# ProProject_ExtBoard-003_2024-07-01.net
KiCad netlist of a schematic drawn in EasyEDA Pro
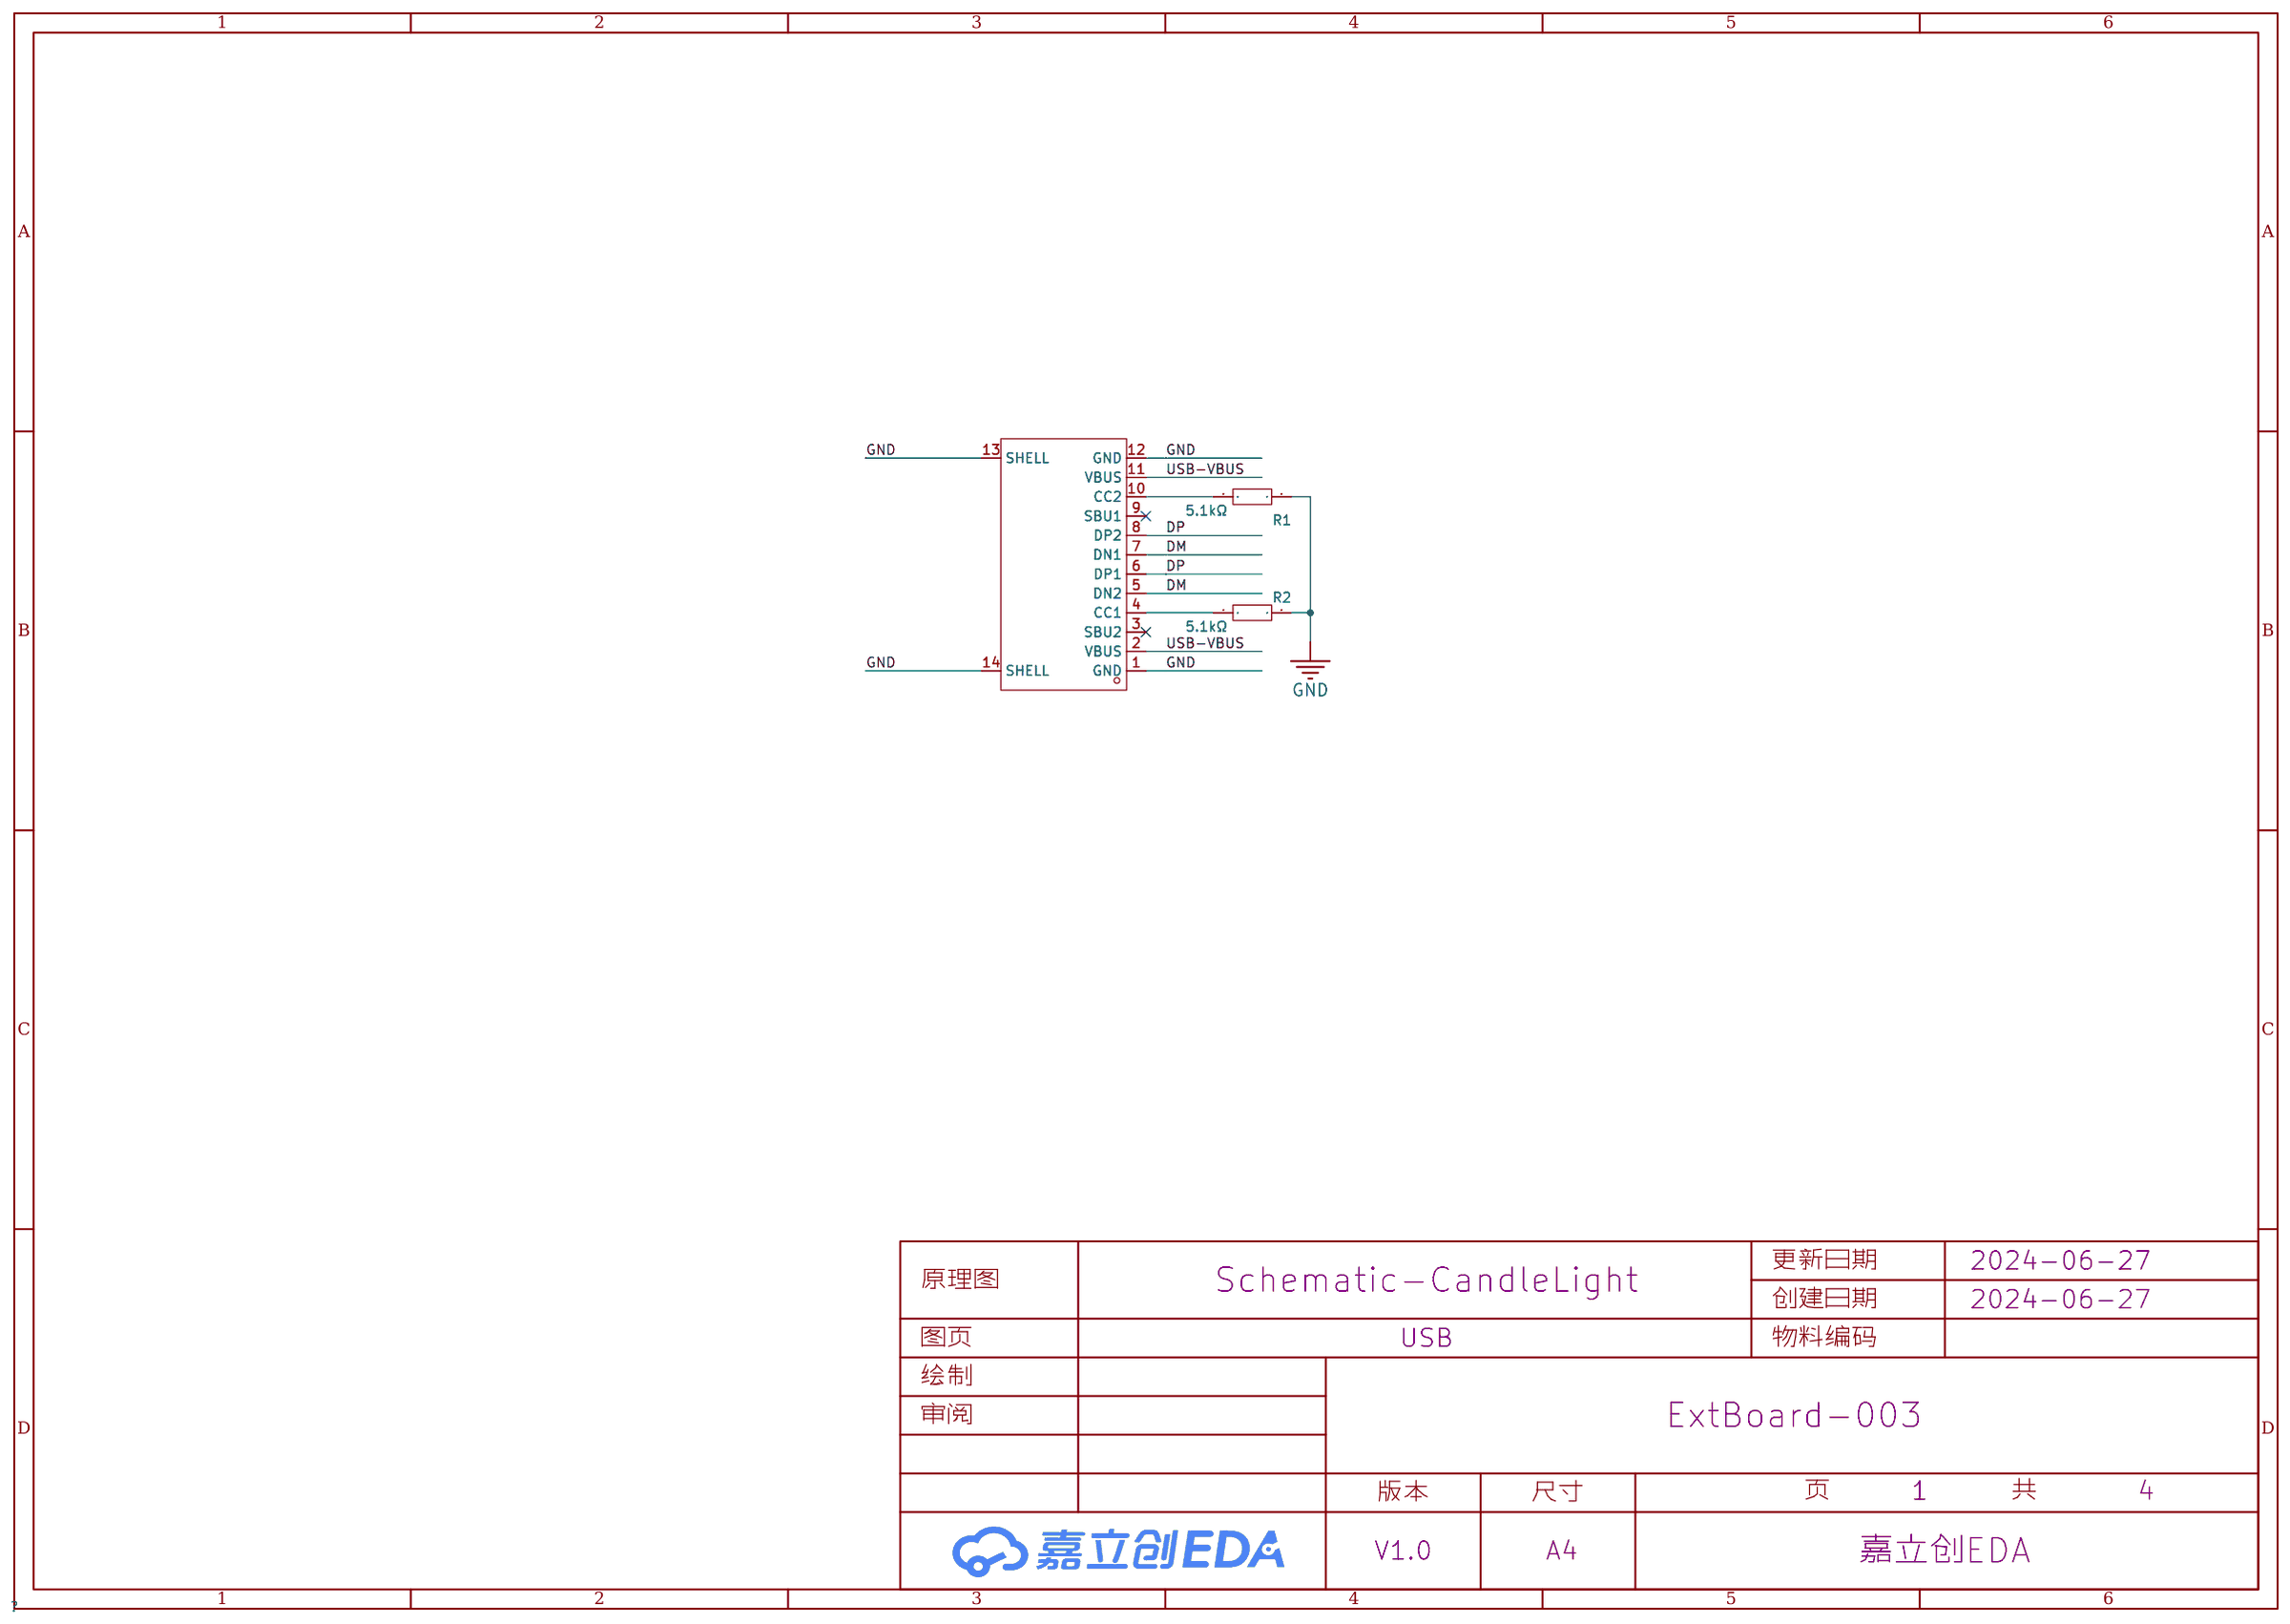
[diagram p0: USB]
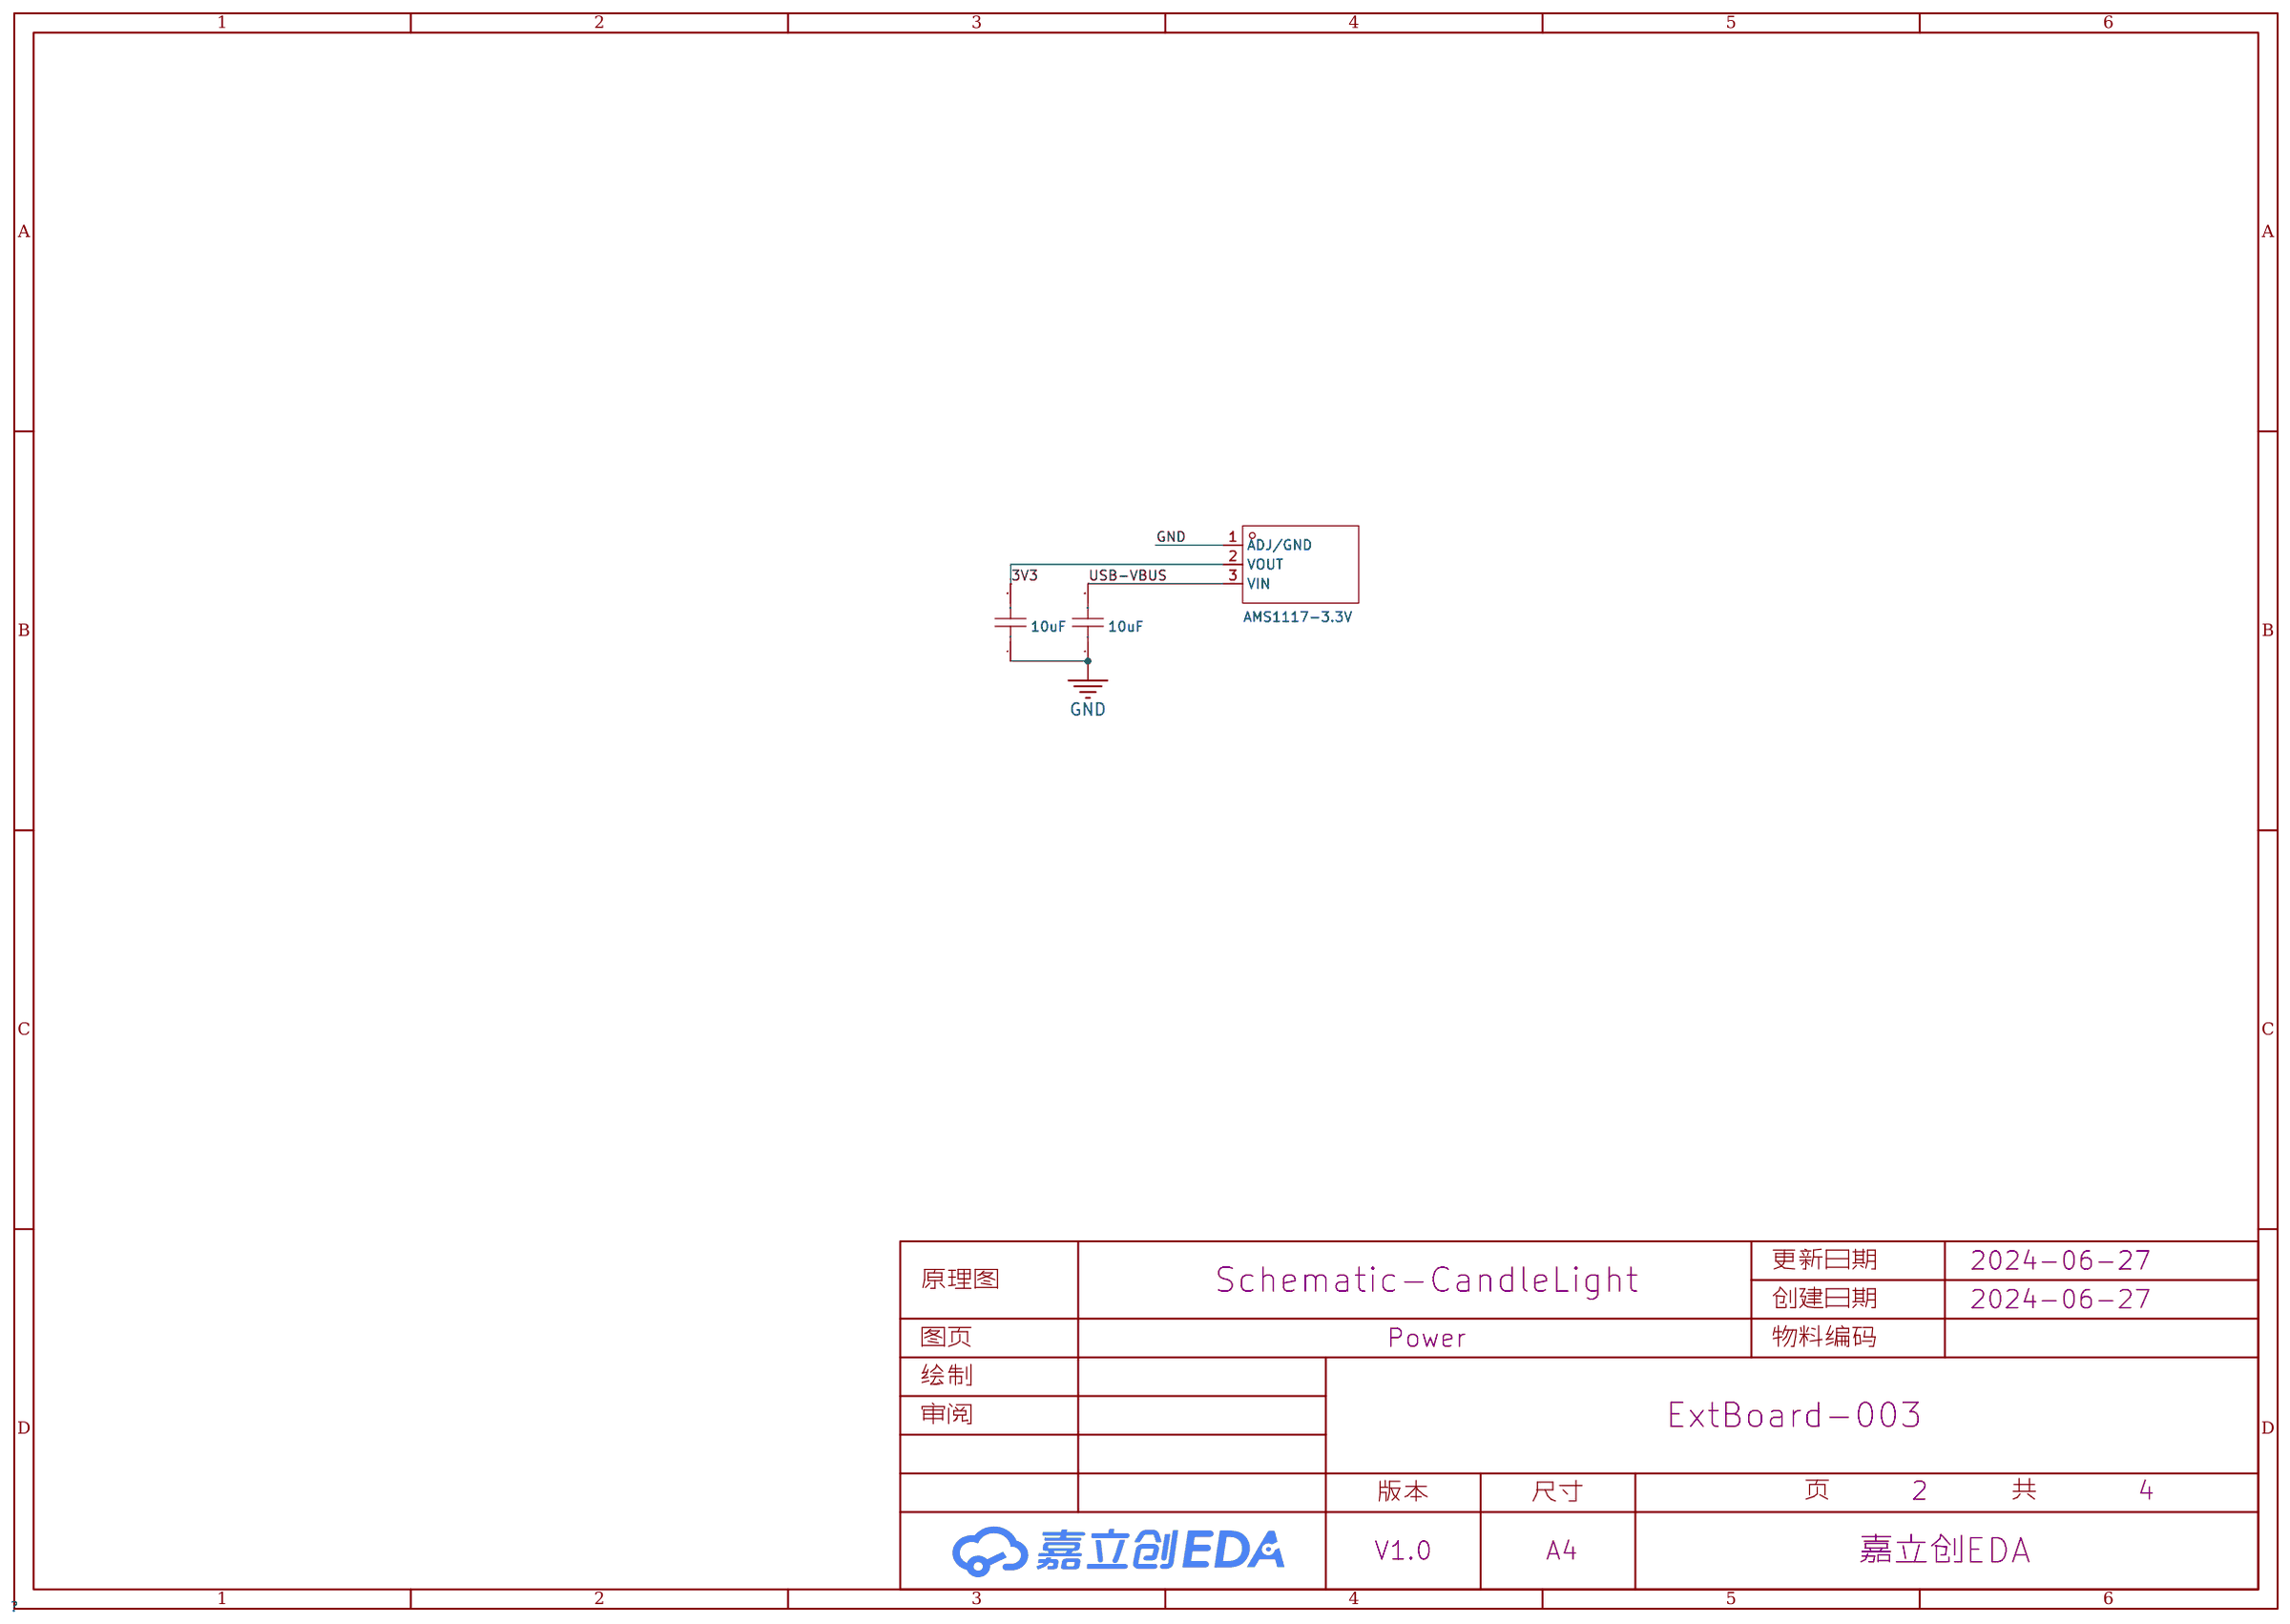
[diagram p1: Power]
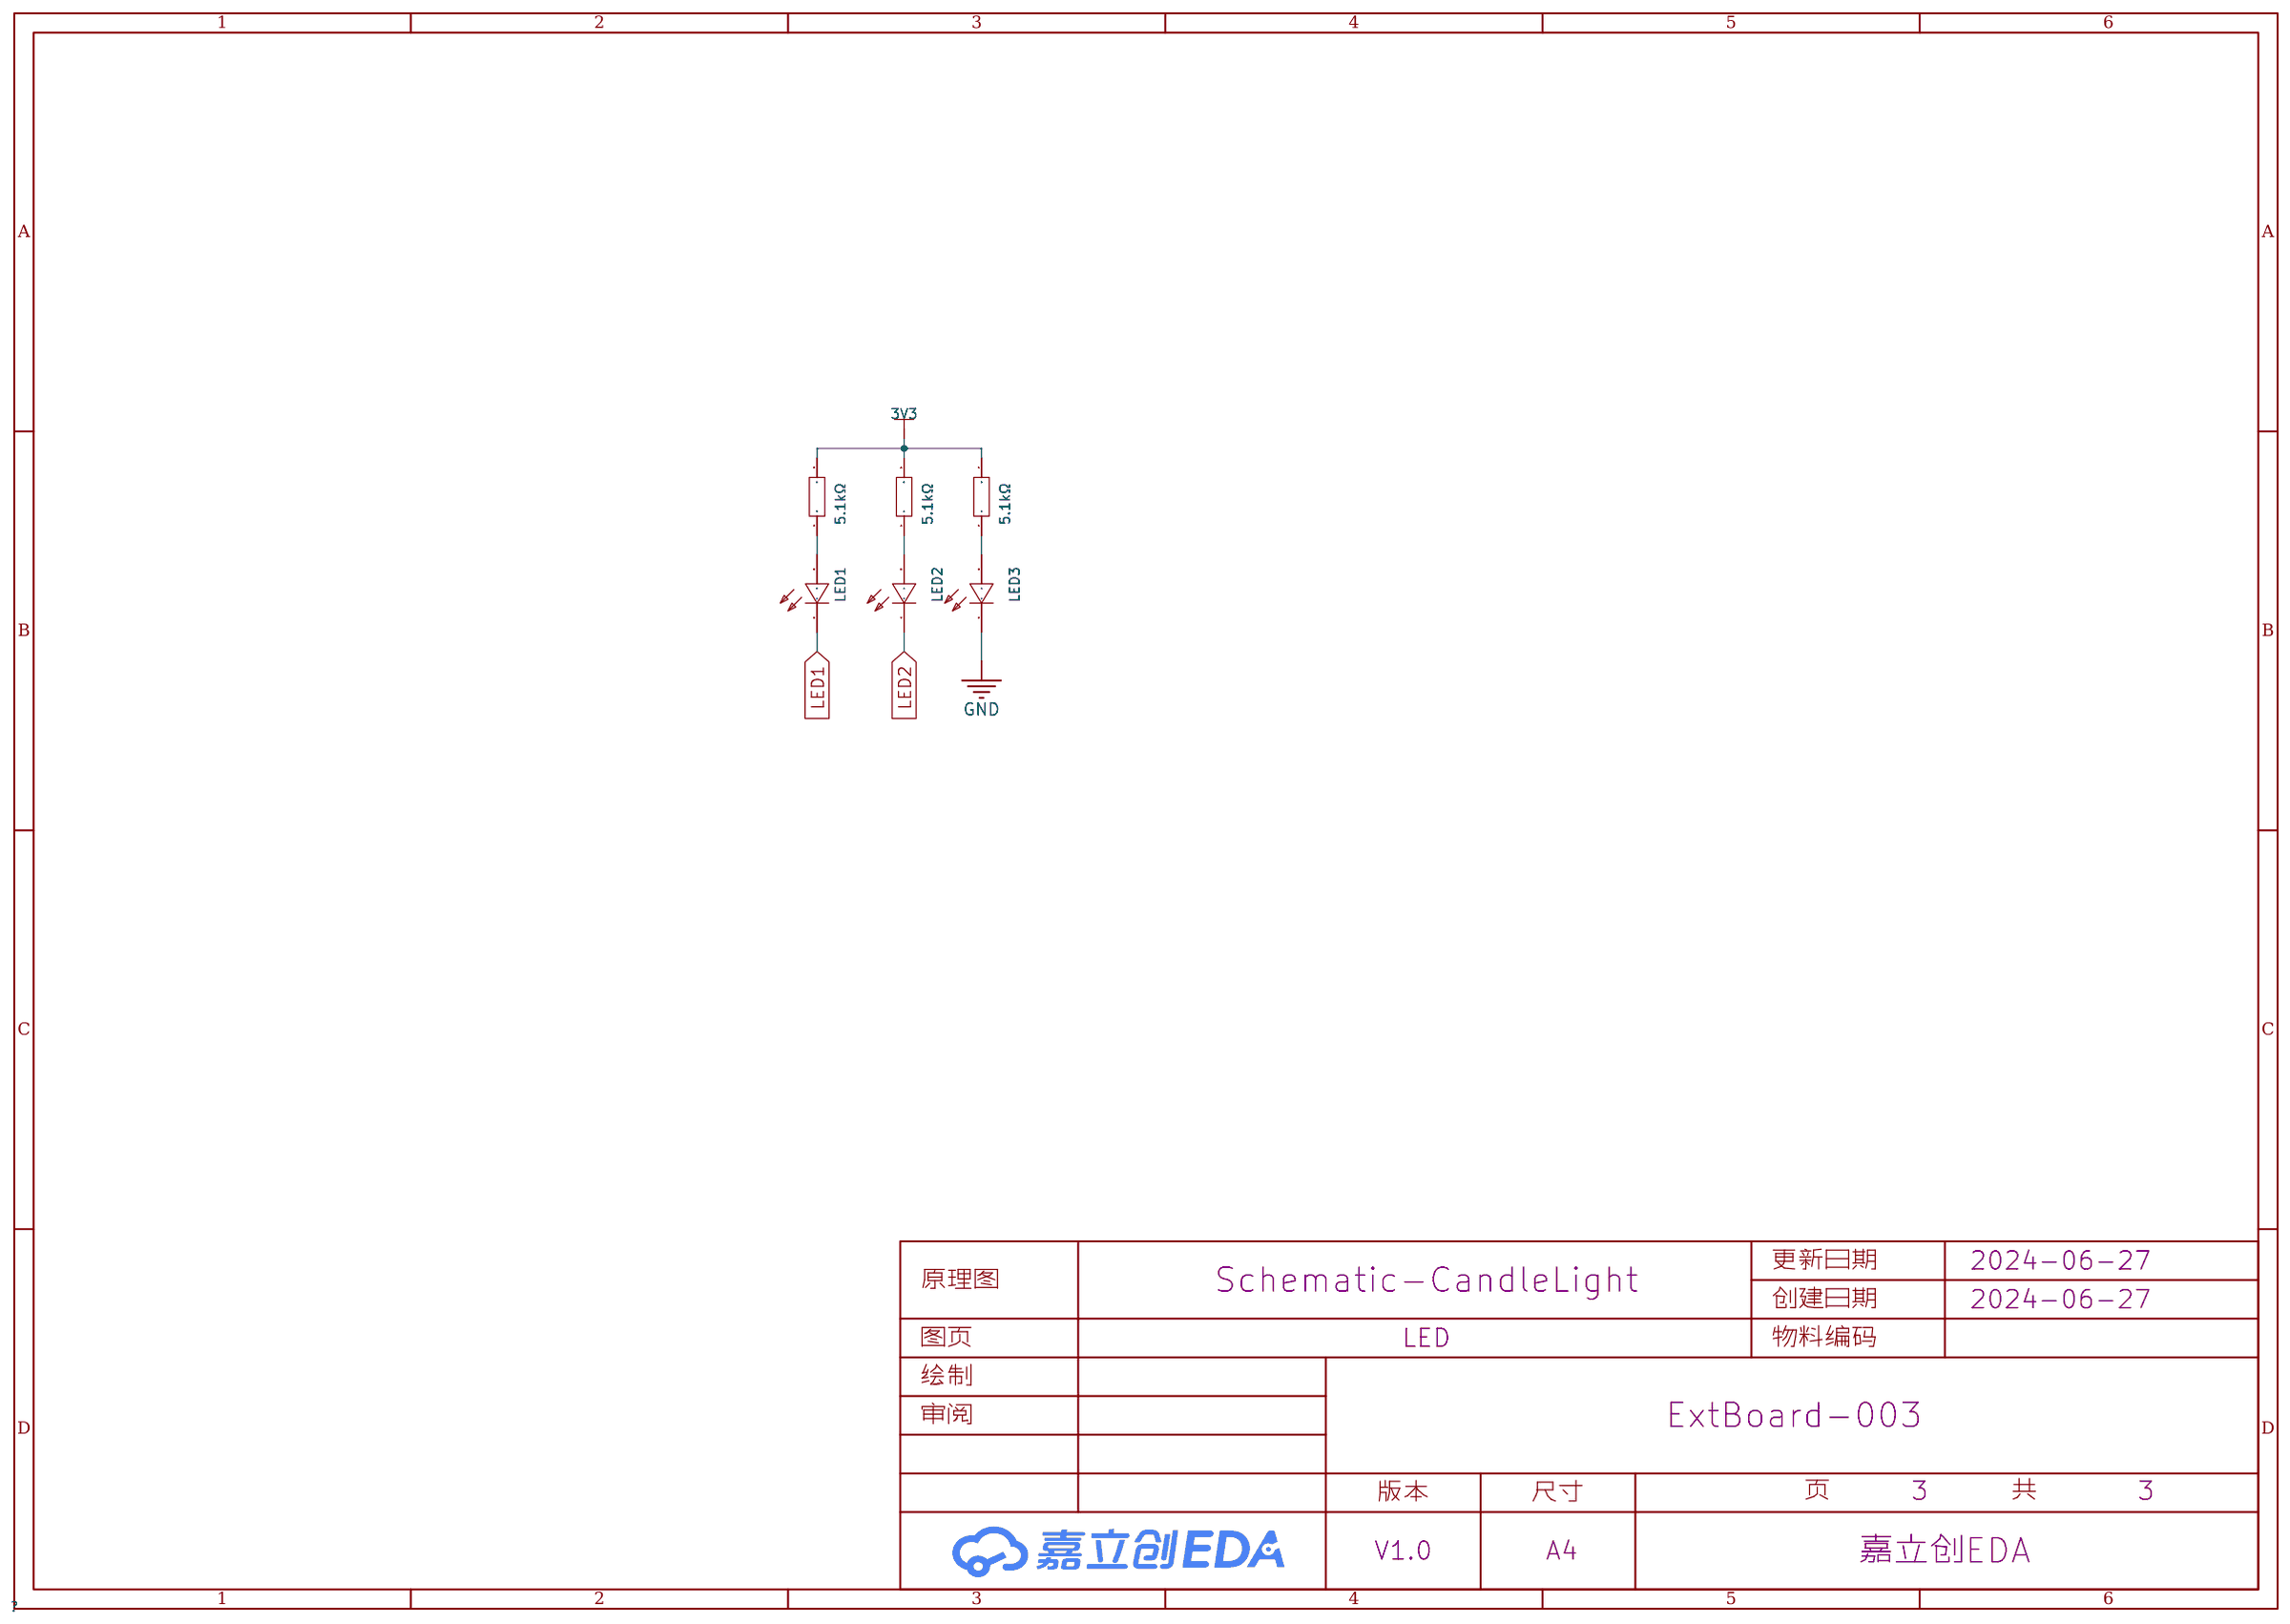
[diagram p2: LED]
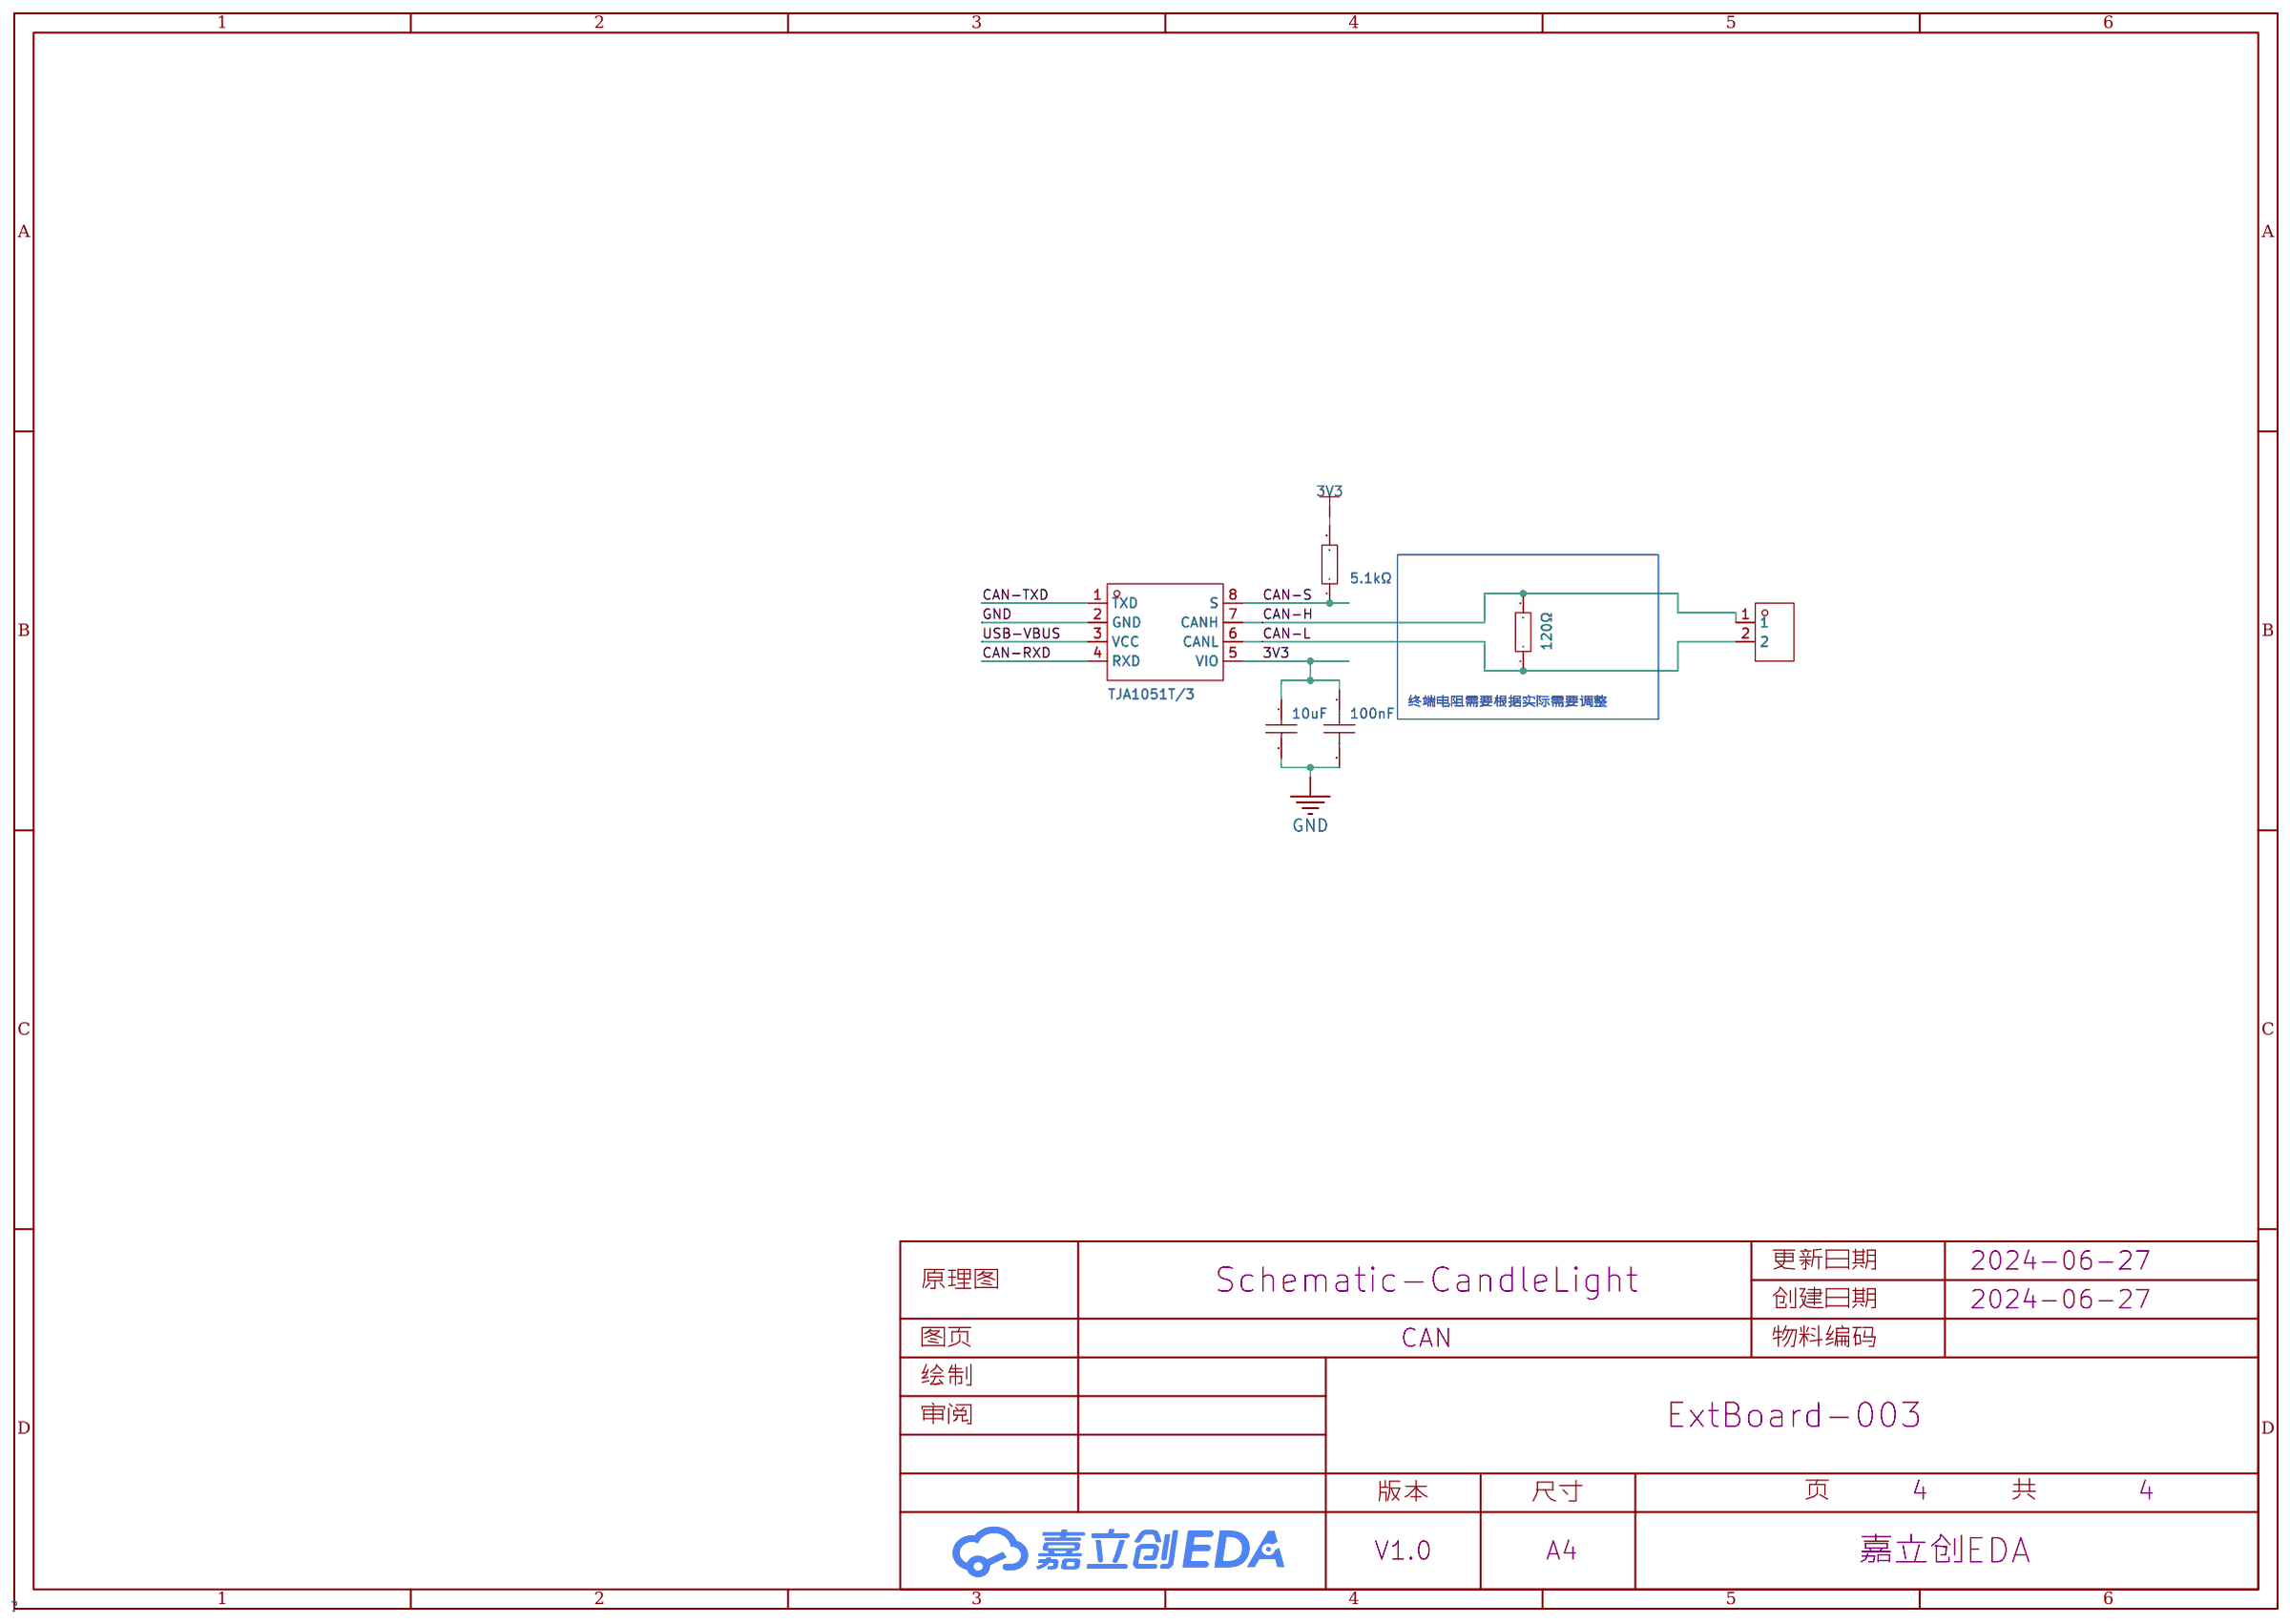
[diagram p3: CAN]
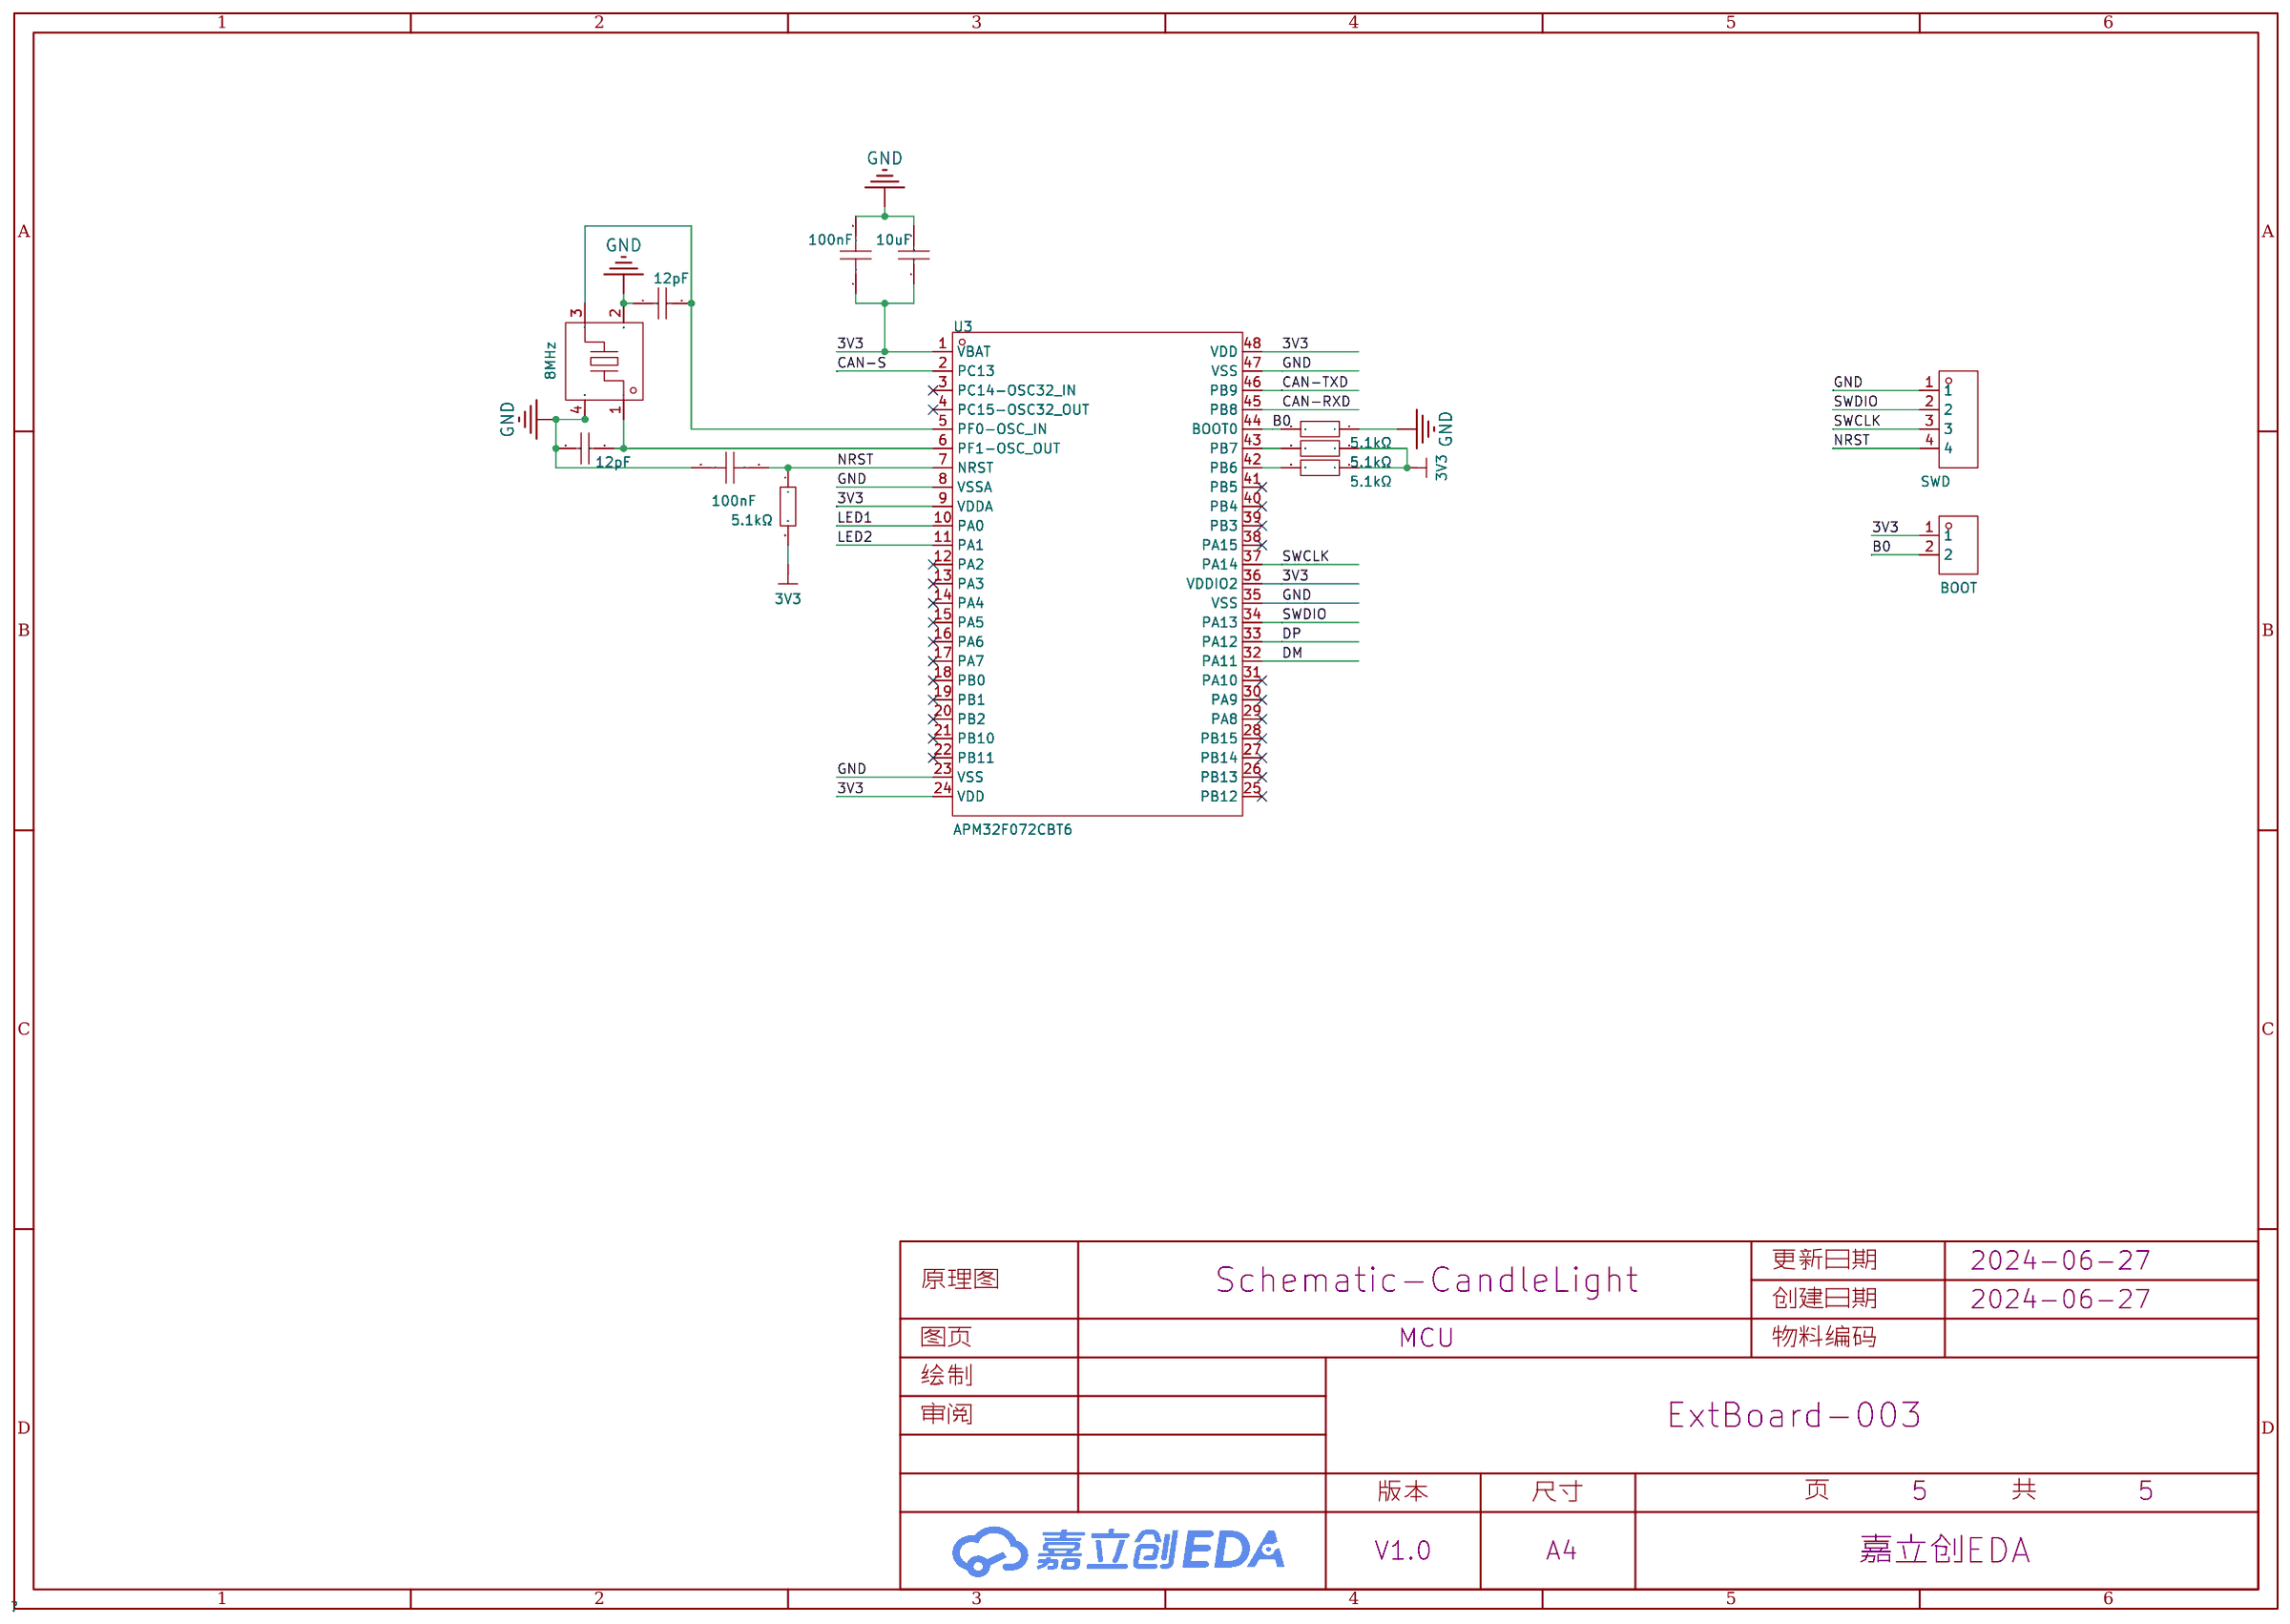
[diagram p4: MCU]

(export (version "E")
  (design (tool "Eeschema 10.0.6"))
  (components
    (comp (ref "R1")
      (value "5.1kΩ")
      (footprint "easyedapro:R0402")
      (description "阻值:5.1kΩ;精度:±1%;功率:62.5mW;温度系数:±100ppm/°C;电阻类型:厚膜电阻;")
      (fields
        (field (name "Manufacturer Part") "0402WGF5101TCE")
        (field (name "Manufacturer") "UNI-ROYAL(厚声)")
      )
      (libsource (lib "easyedapro") (part "0402WGF5101TCE"))
    )
    (comp (ref "R2")
      (value "5.1kΩ")
      (footprint "easyedapro:R0402")
      (description "阻值:5.1kΩ;精度:±1%;功率:62.5mW;温度系数:±100ppm/°C;电阻类型:厚膜电阻;")
      (fields
        (field (name "Manufacturer Part") "0402WGF5101TCE")
        (field (name "Manufacturer") "UNI-ROYAL(厚声)")
      )
      (libsource (lib "easyedapro") (part "0402WGF5101TCE"))
    )
    (comp (ref "USB1")
      (value "TYPE-C 16PIN 2MD(073)")
      (footprint "easyedapro:USB-C-SMD_TYPE-C-6PIN-2MD-073")
      (description "连接器类型:Type-C;标准:-;公母:母;端口数量:1;触点数量:16P;安装方式:卧贴;额定电流 - 电源:5A;工作温度范围:-25°C~+85°C;")
      (fields (field (name "Manufacturer") "SHOU HAN(首韩)"))
      (libsource (lib "easyedapro") (part "TYPE-C 16PIN 2MD(073)"))
    )
    (comp (ref "C1")
      (value "10uF")
      (footprint "easyedapro:C0402")
      (description "容值:10uF;精度:±20%;额定电压:10V;材质(温度系数):X5R;")
      (fields
        (field (name "Manufacturer Part") "GRM155R61A106ME44D")
        (field (name "Manufacturer") "muRata(村田)")
      )
      (libsource (lib "easyedapro") (part "GRM155R61A106ME44D"))
    )
    (comp (ref "C2")
      (value "10uF")
      (footprint "easyedapro:C0402")
      (description "容值:10uF;精度:±20%;额定电压:10V;材质(温度系数):X5R;")
      (fields
        (field (name "Manufacturer Part") "GRM155R61A106ME44D")
        (field (name "Manufacturer") "muRata(村田)")
      )
      (libsource (lib "easyedapro") (part "GRM155R61A106ME44D"))
    )
    (comp (ref "Q1")
      (value "AMS1117-3.3V")
      (footprint "easyedapro:SOT-89-3_L4.5-W2.5-P1.50-LS4.2-BR")
      (description "输出类型:固定;输出极性:正;最大输入电压:18V;输出电压:3.3V;输出电流:1A;")
      (fields (field (name "Manufacturer") "MSKSEMI(美森科)"))
      (libsource (lib "easyedapro") (part "AMS1117-3.3V_C5120796"))
    )
    (comp (ref "LED1")
      (value "NCD0603R1")
      (footprint "easyedapro:LED0603-RD_RED")
      (fields (field (name "Manufacturer") "国星光电"))
      (libsource (lib "easyedapro") (part "FC-DA1608HRK-620D"))
    )
    (comp (ref "LED2")
      (value "NCD0603R1")
      (footprint "easyedapro:LED0603-RD_RED")
      (fields (field (name "Manufacturer") "国星光电"))
      (libsource (lib "easyedapro") (part "FC-DA1608HRK-620D"))
    )
    (comp (ref "LED3")
      (value "NCD0603R1")
      (footprint "easyedapro:LED0603-RD_RED")
      (fields (field (name "Manufacturer") "国星光电"))
      (libsource (lib "easyedapro") (part "FC-DA1608HRK-620D"))
    )
    (comp (ref "R3")
      (value "5.1kΩ")
      (footprint "easyedapro:R0402")
      (description "阻值:5.1kΩ;精度:±1%;功率:62.5mW;温度系数:±100ppm/°C;电阻类型:厚膜电阻;")
      (fields
        (field (name "Manufacturer Part") "0402WGF5101TCE")
        (field (name "Manufacturer") "UNI-ROYAL(厚声)")
      )
      (libsource (lib "easyedapro") (part "0402WGF5101TCE"))
    )
    (comp (ref "R4")
      (value "5.1kΩ")
      (footprint "easyedapro:R0402")
      (description "阻值:5.1kΩ;精度:±1%;功率:62.5mW;温度系数:±100ppm/°C;电阻类型:厚膜电阻;")
      (fields
        (field (name "Manufacturer Part") "0402WGF5101TCE")
        (field (name "Manufacturer") "UNI-ROYAL(厚声)")
      )
      (libsource (lib "easyedapro") (part "0402WGF5101TCE"))
    )
    (comp (ref "R5")
      (value "5.1kΩ")
      (footprint "easyedapro:R0402")
      (description "阻值:5.1kΩ;精度:±1%;功率:62.5mW;温度系数:±100ppm/°C;电阻类型:厚膜电阻;")
      (fields
        (field (name "Manufacturer Part") "0402WGF5101TCE")
        (field (name "Manufacturer") "UNI-ROYAL(厚声)")
      )
      (libsource (lib "easyedapro") (part "0402WGF5101TCE"))
    )
    (comp (ref "C3")
      (value "10uF")
      (footprint "easyedapro:C0402")
      (description "容值:10uF;精度:±20%;额定电压:6.3V;材质(温度系数):X5R;")
      (fields
        (field (name "Manufacturer Part") "CL05A106MQ5NUNC")
        (field (name "Manufacturer") "SAMSUNG(三星)")
      )
      (libsource (lib "easyedapro") (part "CL05A106MQ5NUNC"))
    )
    (comp (ref "C4")
      (value "100nF")
      (footprint "easyedapro:C0402")
      (description "容值:100nF;精度:±10%;额定电压:16V;材质(温度系数):X7R;")
      (fields
        (field (name "Manufacturer Part") "CC0402KRX7R7BB104")
        (field (name "Manufacturer") "YAGEO(国巨)")
      )
      (libsource (lib "easyedapro") (part "CC0402KRX7R7BB104"))
    )
    (comp (ref "R6")
      (value "5.1kΩ")
      (footprint "easyedapro:R0402")
      (description "阻值:5.1kΩ;精度:±1%;功率:62.5mW;温度系数:±100ppm/°C;电阻类型:厚膜电阻;")
      (fields
        (field (name "Manufacturer Part") "0402WGF5101TCE")
        (field (name "Manufacturer") "UNI-ROYAL(厚声)")
      )
      (libsource (lib "easyedapro") (part "0402WGF5101TCE"))
    )
    (comp (ref "R7")
      (value "120Ω")
      (footprint "easyedapro:R1206")
      (description "电阻类型:厚膜电阻;阻值:120Ω;精度:±1%;功率:250mW;最大工作电压:200V;温度系数:±100ppm/°C;")
      (fields
        (field (name "Manufacturer Part") "1206W4F1200T5E")
        (field (name "Manufacturer") "UNI-ROYAL(厚声)")
      )
      (libsource (lib "easyedapro") (part "1206W4F1200T5E_C17909"))
    )
    (comp (ref "U1")
      (value "TJA1051T/3")
      (footprint "easyedapro:SOP-8_L4.9-W3.9-P1.27-LS6.0-BL-1")
      (fields (field (name "Manufacturer") "Tokmas(托克马斯)"))
      (libsource (lib "easyedapro") (part "TJA1051T/3"))
    )
    (comp (ref "U2")
      (value "DB125-3.81-2P-GN-S")
      (footprint "easyedapro:CONN-TH_2P-P3.81_L7.4-W7.6")
      (fields (field (name "Manufacturer") "DORABO(地博电气)"))
      (libsource (lib "easyedapro") (part "DB125-3.81-2P"))
    )
    (comp (ref "C5")
      (value "100nF")
      (footprint "easyedapro:C0402")
      (description "容值:100nF;精度:±10%;额定电压:16V;材质(温度系数):X7R;")
      (fields
        (field (name "Manufacturer Part") "CC0402KRX7R7BB104")
        (field (name "Manufacturer") "YAGEO(国巨)")
      )
      (libsource (lib "easyedapro") (part "CC0402KRX7R7BB104"))
    )
    (comp (ref "C6")
      (value "10uF")
      (footprint "easyedapro:C0402")
      (description "容值:10uF;精度:±20%;额定电压:6.3V;材质(温度系数):X5R;")
      (fields
        (field (name "Manufacturer Part") "CL05A106MQ5NUNC")
        (field (name "Manufacturer") "SAMSUNG(三星)")
      )
      (libsource (lib "easyedapro") (part "CL05A106MQ5NUNC"))
    )
    (comp (ref "C7")
      (value "12pF")
      (footprint "easyedapro:C0402")
      (description "容值:12pF;精度:±5%;额定电压:50V;材质(温度系数):C0G;")
      (fields (field (name "Manufacturer Part") "0402CG120J500NT") (field (name "Manufacturer") "FH(风华)"))
      (libsource (lib "easyedapro") (part "0402CG120J500NT"))
    )
    (comp (ref "C8")
      (value "12pF")
      (footprint "easyedapro:C0402")
      (description "容值:12pF;精度:±5%;额定电压:50V;材质(温度系数):C0G;")
      (fields (field (name "Manufacturer Part") "0402CG120J500NT") (field (name "Manufacturer") "FH(风华)"))
      (libsource (lib "easyedapro") (part "0402CG120J500NT"))
    )
    (comp (ref "C9")
      (value "100nF")
      (footprint "easyedapro:C0402")
      (description "容值:100nF;精度:±10%;额定电压:16V;材质(温度系数):X7R;")
      (fields
        (field (name "Manufacturer Part") "CC0402KRX7R7BB104")
        (field (name "Manufacturer") "YAGEO(国巨)")
      )
      (libsource (lib "easyedapro") (part "CC0402KRX7R7BB104"))
    )
    (comp (ref "H1")
      (value "SWD")
      (footprint "easyedapro:HDR-TH_4P-P2.54-V-M")
      (fields (field (name "Manufacturer Part") "PZ254V-11-04P") (field (name "Manufacturer") "XFCN(兴飞)"))
      (libsource (lib "easyedapro") (part "PZ254V-11-04P_C2691448"))
    )
    (comp (ref "H3")
      (value "BOOT")
      (footprint "easyedapro:HDR-TH_2P-P1.27-V-M")
      (fields (field (name "Manufacturer Part") "1.27-1*2P针") (field (name "Manufacturer") "BOOMELE(博穆精密)"))
      (libsource (lib "easyedapro") (part "1.27MM/1*2P"))
    )
    (comp (ref "R8")
      (value "5.1kΩ")
      (footprint "easyedapro:R0402")
      (description "阻值:5.1kΩ;精度:±1%;功率:62.5mW;温度系数:±100ppm/°C;电阻类型:厚膜电阻;")
      (fields
        (field (name "Manufacturer Part") "0402WGF5101TCE")
        (field (name "Manufacturer") "UNI-ROYAL(厚声)")
      )
      (libsource (lib "easyedapro") (part "0402WGF5101TCE"))
    )
    (comp (ref "R9")
      (value "5.1kΩ")
      (footprint "easyedapro:R0402")
      (description "阻值:5.1kΩ;精度:±1%;功率:62.5mW;温度系数:±100ppm/°C;电阻类型:厚膜电阻;")
      (fields
        (field (name "Manufacturer Part") "0402WGF5101TCE")
        (field (name "Manufacturer") "UNI-ROYAL(厚声)")
      )
      (libsource (lib "easyedapro") (part "0402WGF5101TCE"))
    )
    (comp (ref "R10")
      (value "5.1kΩ")
      (footprint "easyedapro:R0402")
      (description "阻值:5.1kΩ;精度:±1%;功率:62.5mW;温度系数:±100ppm/°C;电阻类型:厚膜电阻;")
      (fields
        (field (name "Manufacturer Part") "0402WGF5101TCE")
        (field (name "Manufacturer") "UNI-ROYAL(厚声)")
      )
      (libsource (lib "easyedapro") (part "0402WGF5101TCE"))
    )
    (comp (ref "R11")
      (value "5.1kΩ")
      (footprint "easyedapro:R0402")
      (description "阻值:5.1kΩ;精度:±1%;功率:62.5mW;温度系数:±100ppm/°C;电阻类型:厚膜电阻;")
      (fields
        (field (name "Manufacturer Part") "0402WGF5101TCE")
        (field (name "Manufacturer") "UNI-ROYAL(厚声)")
      )
      (libsource (lib "easyedapro") (part "0402WGF5101TCE"))
    )
    (comp (ref "U3")
      (value "APM32F072CBT6")
      (footprint "easyedapro:LQFP-48_L7.0-W7.0-P0.50-LS9.0-BL")
      (description "CPU内核:CM0;程序存储容量:128KB;RAM总容量:16KB;GPIO端口数量:37;工作电压范围:2V~3.6V;CPU最大主频:48MHz;程序存储器类型:FLASH;")
      (fields (field (name "Manufacturer") "Geehy(珠海极海)"))
      (libsource (lib "easyedapro") (part "APM32F072CBT6"))
    )
    (comp (ref "X1")
      (value "8MHz")
      (footprint "easyedapro:OSC-SMD_4P-L3.2-W2.5-BL")
      (description "晶振类型:贴片晶振;频率:8MHz;常温频差:±10ppm;外接负载电容:12pF;频率稳定度(全温):±30ppm;")
      (fields (field (name "Manufacturer Part") "X32258MOB4SI") (field (name "Manufacturer") "YXC(扬兴晶振)"))
      (libsource (lib "easyedapro") (part "X32258MOB4SI"))
    )
  )
  (nets
    (net (code "1") (name "3V3") (class "Default")
      (node (ref "C1") (pin "2") (pinfunction "2_2") (pintype "input"))
      (node (ref "C3") (pin "1") (pinfunction "1_1") (pintype "input"))
      (node (ref "C4") (pin "1") (pinfunction "1_1") (pintype "unspecified"))
      (node (ref "C5") (pin "1") (pinfunction "1_1") (pintype "unspecified"))
      (node (ref "C6") (pin "1") (pinfunction "1_1") (pintype "input"))
      (node (ref "H3") (pin "1") (pinfunction "1_1") (pintype "input"))
      (node (ref "Q1") (pin "2") (pinfunction "VOUT_2") (pintype "input"))
      (node (ref "R10") (pin "1") (pinfunction "1_1") (pintype "input"))
      (node (ref "R11") (pin "2") (pinfunction "2_2") (pintype "input"))
      (node (ref "R3") (pin "2") (pinfunction "2_2") (pintype "input"))
      (node (ref "R4") (pin "2") (pinfunction "2_2") (pintype "input"))
      (node (ref "R5") (pin "2") (pinfunction "2_2") (pintype "input"))
      (node (ref "R6") (pin "2") (pinfunction "2_2") (pintype "input"))
      (node (ref "R9") (pin "1") (pinfunction "1_1") (pintype "input"))
      (node (ref "U1") (pin "5") (pinfunction "VIO_5") (pintype "unspecified"))
      (node (ref "U3") (pin "1") (pinfunction "VBAT_1") (pintype "unspecified"))
      (node (ref "U3") (pin "24") (pinfunction "VDD_24") (pintype "unspecified"))
      (node (ref "U3") (pin "36") (pinfunction "VDDIO2_36") (pintype "unspecified"))
      (node (ref "U3") (pin "48") (pinfunction "VDD_48") (pintype "unspecified"))
      (node (ref "U3") (pin "9") (pinfunction "VDDA_9") (pintype "unspecified"))
    )
    (net (code "2") (name "B0") (class "Default")
      (node (ref "H3") (pin "2") (pinfunction "2_2") (pintype "input"))
      (node (ref "R8") (pin "2") (pinfunction "2_2") (pintype "input"))
      (node (ref "U3") (pin "44") (pinfunction "BOOT0_44") (pintype "unspecified"))
    )
    (net (code "3") (name "CAN-H") (class "Default")
      (node (ref "R7") (pin "2") (pinfunction "2_2") (pintype "input"))
      (node (ref "U1") (pin "7") (pinfunction "CANH_7") (pintype "unspecified"))
      (node (ref "U2") (pin "1") (pinfunction "1_1") (pintype "unspecified"))
    )
    (net (code "4") (name "CAN-L") (class "Default")
      (node (ref "R7") (pin "1") (pinfunction "1_1") (pintype "input"))
      (node (ref "U1") (pin "6") (pinfunction "CANL_6") (pintype "unspecified"))
      (node (ref "U2") (pin "2") (pinfunction "2_2") (pintype "unspecified"))
    )
    (net (code "5") (name "CAN-RXD") (class "Default")
      (node (ref "U1") (pin "4") (pinfunction "RXD_4") (pintype "unspecified"))
      (node (ref "U3") (pin "45") (pinfunction "PB8_45") (pintype "unspecified"))
    )
    (net (code "6") (name "CAN-S") (class "Default")
      (node (ref "R6") (pin "1") (pinfunction "1_1") (pintype "input"))
      (node (ref "U1") (pin "8") (pinfunction "S_8") (pintype "unspecified"))
      (node (ref "U3") (pin "2") (pinfunction "PC13_2") (pintype "unspecified"))
    )
    (net (code "7") (name "CAN-TXD") (class "Default")
      (node (ref "U1") (pin "1") (pinfunction "TXD_1") (pintype "unspecified"))
      (node (ref "U3") (pin "46") (pinfunction "PB9_46") (pintype "unspecified"))
    )
    (net (code "8") (name "DM") (class "Default")
      (node (ref "U3") (pin "32") (pinfunction "PA11_32") (pintype "unspecified"))
      (node (ref "USB1") (pin "5") (pinfunction "DN2_5") (pintype "unspecified"))
      (node (ref "USB1") (pin "7") (pinfunction "DN1_7") (pintype "unspecified"))
    )
    (net (code "9") (name "DP") (class "Default")
      (node (ref "U3") (pin "33") (pinfunction "PA12_33") (pintype "unspecified"))
      (node (ref "USB1") (pin "6") (pinfunction "DP1_6") (pintype "unspecified"))
      (node (ref "USB1") (pin "8") (pinfunction "DP2_8") (pintype "unspecified"))
    )
    (net (code "10") (name "GND") (class "Default")
      (node (ref "C1") (pin "1") (pinfunction "1_1") (pintype "input"))
      (node (ref "C2") (pin "1") (pinfunction "1_1") (pintype "input"))
      (node (ref "C3") (pin "2") (pinfunction "2_2") (pintype "input"))
      (node (ref "C4") (pin "2") (pinfunction "2_2") (pintype "unspecified"))
      (node (ref "C5") (pin "2") (pinfunction "2_2") (pintype "unspecified"))
      (node (ref "C6") (pin "2") (pinfunction "2_2") (pintype "input"))
      (node (ref "C7") (pin "1") (pinfunction "1_1") (pintype "input"))
      (node (ref "C8") (pin "1") (pinfunction "1_1") (pintype "input"))
      (node (ref "C9") (pin "2") (pinfunction "2_2") (pintype "unspecified"))
      (node (ref "H1") (pin "1") (pinfunction "1_1") (pintype "unspecified"))
      (node (ref "LED3") (pin "1") (pinfunction "K_1") (pintype "input"))
      (node (ref "Q1") (pin "1") (pinfunction "ADJ/GND_1") (pintype "input"))
      (node (ref "R1") (pin "2") (pinfunction "2_2") (pintype "input"))
      (node (ref "R2") (pin "2") (pinfunction "2_2") (pintype "input"))
      (node (ref "R8") (pin "1") (pinfunction "1_1") (pintype "input"))
      (node (ref "U1") (pin "2") (pinfunction "GND_2") (pintype "unspecified"))
      (node (ref "U3") (pin "23") (pinfunction "VSS_23") (pintype "unspecified"))
      (node (ref "U3") (pin "35") (pinfunction "VSS_35") (pintype "unspecified"))
      (node (ref "U3") (pin "47") (pinfunction "VSS_47") (pintype "unspecified"))
      (node (ref "U3") (pin "8") (pinfunction "VSSA_8") (pintype "unspecified"))
      (node (ref "USB1") (pin "1") (pinfunction "GND_1") (pintype "unspecified"))
      (node (ref "USB1") (pin "12") (pinfunction "GND_12") (pintype "unspecified"))
      (node (ref "USB1") (pin "13") (pinfunction "SHELL_13") (pintype "unspecified"))
      (node (ref "USB1") (pin "14") (pinfunction "SHELL_14") (pintype "unspecified"))
      (node (ref "X1") (pin "2") (pinfunction "GND_2") (pintype "input"))
      (node (ref "X1") (pin "4") (pinfunction "GND_4") (pintype "input"))
    )
    (net (code "11") (name "LED1") (class "Default")
      (node (ref "LED1") (pin "1") (pinfunction "K_1") (pintype "input"))
      (node (ref "U3") (pin "10") (pinfunction "PA0_10") (pintype "unspecified"))
    )
    (net (code "12") (name "LED2") (class "Default")
      (node (ref "LED2") (pin "1") (pinfunction "K_1") (pintype "input"))
      (node (ref "U3") (pin "11") (pinfunction "PA1_11") (pintype "unspecified"))
    )
    (net (code "13") (name "NRST") (class "Default")
      (node (ref "C9") (pin "1") (pinfunction "1_1") (pintype "unspecified"))
      (node (ref "H1") (pin "4") (pinfunction "4_4") (pintype "unspecified"))
      (node (ref "R11") (pin "1") (pinfunction "1_1") (pintype "input"))
      (node (ref "U3") (pin "7") (pinfunction "NRST_7") (pintype "unspecified"))
    )
    (net (code "14") (name "Net-(LED1-A)") (class "Default")
      (node (ref "LED1") (pin "2") (pinfunction "A_2") (pintype "input"))
      (node (ref "R3") (pin "1") (pinfunction "1_1") (pintype "input"))
    )
    (net (code "15") (name "Net-(LED2-A)") (class "Default")
      (node (ref "LED2") (pin "2") (pinfunction "A_2") (pintype "input"))
      (node (ref "R4") (pin "1") (pinfunction "1_1") (pintype "input"))
    )
    (net (code "16") (name "Net-(LED3-A)") (class "Default")
      (node (ref "LED3") (pin "2") (pinfunction "A_2") (pintype "input"))
      (node (ref "R5") (pin "1") (pinfunction "1_1") (pintype "input"))
    )
    (net (code "17") (name "Net-(U3-PB6)") (class "Default")
      (node (ref "R10") (pin "2") (pinfunction "2_2") (pintype "input"))
      (node (ref "U3") (pin "42") (pinfunction "PB6_42") (pintype "unspecified"))
    )
    (net (code "18") (name "Net-(U3-PB7)") (class "Default")
      (node (ref "R9") (pin "2") (pinfunction "2_2") (pintype "input"))
      (node (ref "U3") (pin "43") (pinfunction "PB7_43") (pintype "unspecified"))
    )
    (net (code "19") (name "Net-(U3-PF0-OSC_IN)") (class "Default")
      (node (ref "C7") (pin "2") (pinfunction "2_2") (pintype "input"))
      (node (ref "U3") (pin "5") (pinfunction "PF0-OSC_IN_5") (pintype "unspecified"))
      (node (ref "X1") (pin "3") (pinfunction "3_3") (pintype "input"))
    )
    (net (code "20") (name "Net-(U3-PF1-OSC_OUT)") (class "Default")
      (node (ref "C8") (pin "2") (pinfunction "2_2") (pintype "input"))
      (node (ref "U3") (pin "6") (pinfunction "PF1-OSC_OUT_6") (pintype "unspecified"))
      (node (ref "X1") (pin "1") (pinfunction "1_1") (pintype "input"))
    )
    (net (code "21") (name "Net-(USB1-CC1)") (class "Default")
      (node (ref "R2") (pin "1") (pinfunction "1_1") (pintype "input"))
      (node (ref "USB1") (pin "4") (pinfunction "CC1_4") (pintype "unspecified"))
    )
    (net (code "22") (name "Net-(USB1-CC2)") (class "Default")
      (node (ref "R1") (pin "1") (pinfunction "1_1") (pintype "input"))
      (node (ref "USB1") (pin "10") (pinfunction "CC2_10") (pintype "unspecified"))
    )
    (net (code "23") (name "SWCLK") (class "Default")
      (node (ref "H1") (pin "3") (pinfunction "3_3") (pintype "unspecified"))
      (node (ref "U3") (pin "37") (pinfunction "PA14_37") (pintype "unspecified"))
    )
    (net (code "24") (name "SWDIO") (class "Default")
      (node (ref "H1") (pin "2") (pinfunction "2_2") (pintype "unspecified"))
      (node (ref "U3") (pin "34") (pinfunction "PA13_34") (pintype "unspecified"))
    )
    (net (code "25") (name "USB-VBUS") (class "Default")
      (node (ref "C2") (pin "2") (pinfunction "2_2") (pintype "input"))
      (node (ref "Q1") (pin "3") (pinfunction "VIN_3") (pintype "input"))
      (node (ref "U1") (pin "3") (pinfunction "VCC_3") (pintype "unspecified"))
      (node (ref "USB1") (pin "11") (pinfunction "VBUS_11") (pintype "unspecified"))
      (node (ref "USB1") (pin "2") (pinfunction "VBUS_2") (pintype "unspecified"))
    )
    (net (code "26") (name "unconnected-(U3-PA2-Pad12)") (class "Default")
      (node (ref "U3") (pin "12") (pinfunction "PA2_12") (pintype "unspecified+no_connect"))
    )
    (net (code "27") (name "unconnected-(U3-PA3-Pad13)") (class "Default")
      (node (ref "U3") (pin "13") (pinfunction "PA3_13") (pintype "unspecified+no_connect"))
    )
    (net (code "28") (name "unconnected-(U3-PA4-Pad14)") (class "Default")
      (node (ref "U3") (pin "14") (pinfunction "PA4_14") (pintype "unspecified+no_connect"))
    )
    (net (code "29") (name "unconnected-(U3-PA5-Pad15)") (class "Default")
      (node (ref "U3") (pin "15") (pinfunction "PA5_15") (pintype "unspecified+no_connect"))
    )
    (net (code "30") (name "unconnected-(U3-PA6-Pad16)") (class "Default")
      (node (ref "U3") (pin "16") (pinfunction "PA6_16") (pintype "unspecified+no_connect"))
    )
    (net (code "31") (name "unconnected-(U3-PA7-Pad17)") (class "Default")
      (node (ref "U3") (pin "17") (pinfunction "PA7_17") (pintype "unspecified+no_connect"))
    )
    (net (code "32") (name "unconnected-(U3-PA8-Pad29)") (class "Default")
      (node (ref "U3") (pin "29") (pinfunction "PA8_29") (pintype "unspecified+no_connect"))
    )
    (net (code "33") (name "unconnected-(U3-PA9-Pad30)") (class "Default")
      (node (ref "U3") (pin "30") (pinfunction "PA9_30") (pintype "unspecified+no_connect"))
    )
    (net (code "34") (name "unconnected-(U3-PA10-Pad31)") (class "Default")
      (node (ref "U3") (pin "31") (pinfunction "PA10_31") (pintype "unspecified+no_connect"))
    )
    (net (code "35") (name "unconnected-(U3-PA15-Pad38)") (class "Default")
      (node (ref "U3") (pin "38") (pinfunction "PA15_38") (pintype "unspecified+no_connect"))
    )
    (net (code "36") (name "unconnected-(U3-PB0-Pad18)") (class "Default")
      (node (ref "U3") (pin "18") (pinfunction "PB0_18") (pintype "unspecified+no_connect"))
    )
    (net (code "37") (name "unconnected-(U3-PB1-Pad19)") (class "Default")
      (node (ref "U3") (pin "19") (pinfunction "PB1_19") (pintype "unspecified+no_connect"))
    )
    (net (code "38") (name "unconnected-(U3-PB2-Pad20)") (class "Default")
      (node (ref "U3") (pin "20") (pinfunction "PB2_20") (pintype "unspecified+no_connect"))
    )
    (net (code "39") (name "unconnected-(U3-PB3-Pad39)") (class "Default")
      (node (ref "U3") (pin "39") (pinfunction "PB3_39") (pintype "unspecified+no_connect"))
    )
    (net (code "40") (name "unconnected-(U3-PB4-Pad40)") (class "Default")
      (node (ref "U3") (pin "40") (pinfunction "PB4_40") (pintype "unspecified+no_connect"))
    )
    (net (code "41") (name "unconnected-(U3-PB5-Pad41)") (class "Default")
      (node (ref "U3") (pin "41") (pinfunction "PB5_41") (pintype "unspecified+no_connect"))
    )
    (net (code "42") (name "unconnected-(U3-PB10-Pad21)") (class "Default")
      (node (ref "U3") (pin "21") (pinfunction "PB10_21") (pintype "unspecified+no_connect"))
    )
    (net (code "43") (name "unconnected-(U3-PB11-Pad22)") (class "Default")
      (node (ref "U3") (pin "22") (pinfunction "PB11_22") (pintype "unspecified+no_connect"))
    )
    (net (code "44") (name "unconnected-(U3-PB12-Pad25)") (class "Default")
      (node (ref "U3") (pin "25") (pinfunction "PB12_25") (pintype "unspecified+no_connect"))
    )
    (net (code "45") (name "unconnected-(U3-PB13-Pad26)") (class "Default")
      (node (ref "U3") (pin "26") (pinfunction "PB13_26") (pintype "unspecified+no_connect"))
    )
    (net (code "46") (name "unconnected-(U3-PB14-Pad27)") (class "Default")
      (node (ref "U3") (pin "27") (pinfunction "PB14_27") (pintype "unspecified+no_connect"))
    )
    (net (code "47") (name "unconnected-(U3-PB15-Pad28)") (class "Default")
      (node (ref "U3") (pin "28") (pinfunction "PB15_28") (pintype "unspecified+no_connect"))
    )
    (net (code "48") (name "unconnected-(U3-PC14-OSC32_IN-Pad3)") (class "Default")
      (node (ref "U3") (pin "3") (pinfunction "PC14-OSC32_IN_3") (pintype "unspecified+no_connect"))
    )
    (net (code "49") (name "unconnected-(U3-PC15-OSC32_OUT-Pad4)") (class "Default")
      (node (ref "U3") (pin "4") (pinfunction "PC15-OSC32_OUT_4") (pintype "unspecified+no_connect"))
    )
    (net (code "50") (name "unconnected-(USB1-SBU1-Pad9)") (class "Default")
      (node (ref "USB1") (pin "9") (pinfunction "SBU1_9") (pintype "unspecified+no_connect"))
    )
    (net (code "51") (name "unconnected-(USB1-SBU2-Pad3)") (class "Default")
      (node (ref "USB1") (pin "3") (pinfunction "SBU2_3") (pintype "unspecified+no_connect"))
    )
  )
)
